# BMS_Battery_Connections.net
KiCad netlist of a schematic drawn in Altium Designer
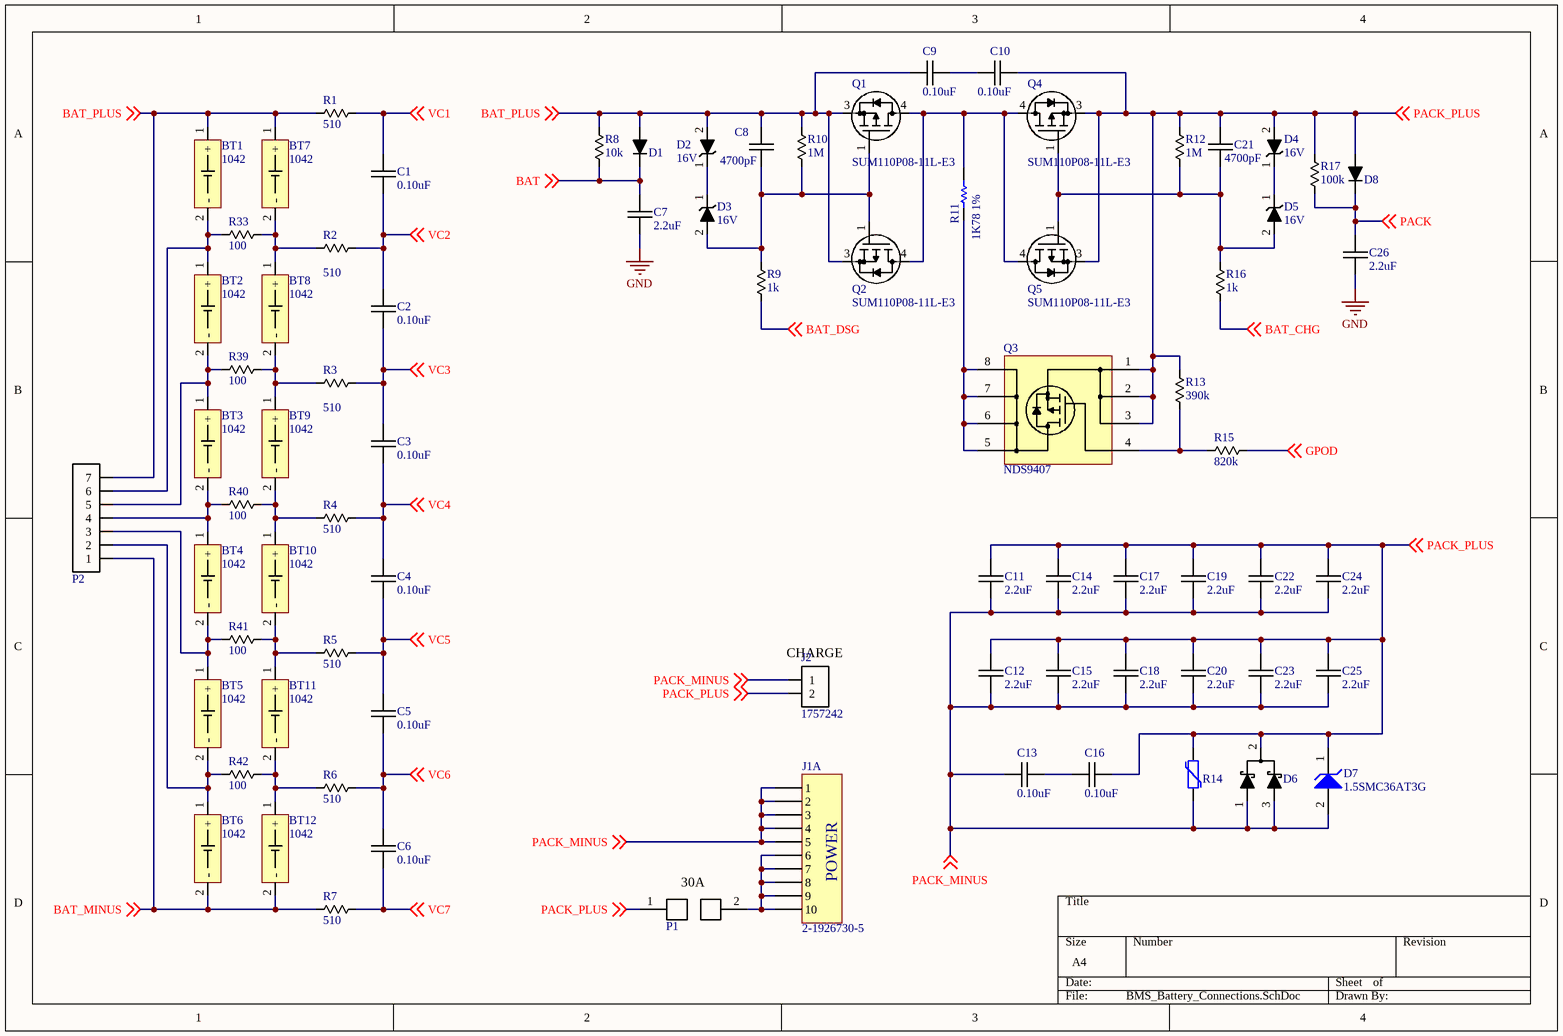
[diagram p0: BMS_Battery_Connections.SchDoc]

(export (version "E")
  (design (tool "Eeschema 10.0.6"))
  (components
    (comp (ref "BT1")
      (value "1042")
      (footprint "KEYSTONE_1042")
      (description "Battery Holder, 18650, SMD")
      (fields (field (name "PART NUMBER") "CONN-00077") (field (name "MANUFACTURER") "Keystone"))
      (libsource (lib "Connectors$") (part "CONN-00077"))
    )
    (comp (ref "BT2")
      (value "1042")
      (footprint "KEYSTONE_1042")
      (description "Battery Holder, 18650, SMD")
      (fields (field (name "PART NUMBER") "CONN-00077") (field (name "MANUFACTURER") "Keystone"))
      (libsource (lib "Connectors$") (part "CONN-00077"))
    )
    (comp (ref "BT3")
      (value "1042")
      (footprint "KEYSTONE_1042")
      (description "Battery Holder, 18650, SMD")
      (fields (field (name "PART NUMBER") "CONN-00077") (field (name "MANUFACTURER") "Keystone"))
      (libsource (lib "Connectors$") (part "CONN-00077"))
    )
    (comp (ref "BT4")
      (value "1042")
      (footprint "KEYSTONE_1042")
      (description "Battery Holder, 18650, SMD")
      (fields (field (name "PART NUMBER") "CONN-00077") (field (name "MANUFACTURER") "Keystone"))
      (libsource (lib "Connectors$") (part "CONN-00077"))
    )
    (comp (ref "BT5")
      (value "1042")
      (footprint "KEYSTONE_1042")
      (description "Battery Holder, 18650, SMD")
      (fields (field (name "PART NUMBER") "CONN-00077") (field (name "MANUFACTURER") "Keystone"))
      (libsource (lib "Connectors$") (part "CONN-00077"))
    )
    (comp (ref "BT6")
      (value "1042")
      (footprint "KEYSTONE_1042")
      (description "Battery Holder, 18650, SMD")
      (fields (field (name "PART NUMBER") "CONN-00077") (field (name "MANUFACTURER") "Keystone"))
      (libsource (lib "Connectors$") (part "CONN-00077"))
    )
    (comp (ref "BT7")
      (value "1042")
      (footprint "KEYSTONE_1042")
      (description "Battery Holder, 18650, SMD")
      (fields (field (name "PART NUMBER") "CONN-00077") (field (name "MANUFACTURER") "Keystone"))
      (libsource (lib "Connectors$") (part "CONN-00077"))
    )
    (comp (ref "BT8")
      (value "1042")
      (footprint "KEYSTONE_1042")
      (description "Battery Holder, 18650, SMD")
      (fields (field (name "PART NUMBER") "CONN-00077") (field (name "MANUFACTURER") "Keystone"))
      (libsource (lib "Connectors$") (part "CONN-00077"))
    )
    (comp (ref "BT9")
      (value "1042")
      (footprint "KEYSTONE_1042")
      (description "Battery Holder, 18650, SMD")
      (fields (field (name "PART NUMBER") "CONN-00077") (field (name "MANUFACTURER") "Keystone"))
      (libsource (lib "Connectors$") (part "CONN-00077"))
    )
    (comp (ref "BT10")
      (value "1042")
      (footprint "KEYSTONE_1042")
      (description "Battery Holder, 18650, SMD")
      (fields (field (name "PART NUMBER") "CONN-00077") (field (name "MANUFACTURER") "Keystone"))
      (libsource (lib "Connectors$") (part "CONN-00077"))
    )
    (comp (ref "BT11")
      (value "1042")
      (footprint "KEYSTONE_1042")
      (description "Battery Holder, 18650, SMD")
      (fields (field (name "PART NUMBER") "CONN-00077") (field (name "MANUFACTURER") "Keystone"))
      (libsource (lib "Connectors$") (part "CONN-00077"))
    )
    (comp (ref "BT12")
      (value "1042")
      (footprint "KEYSTONE_1042")
      (description "Battery Holder, 18650, SMD")
      (fields (field (name "PART NUMBER") "CONN-00077") (field (name "MANUFACTURER") "Keystone"))
      (libsource (lib "Connectors$") (part "CONN-00077"))
    )
    (comp (ref "C1")
      (value "0.10uF")
      (footprint "chip_0805")
      (description "CAP, 0.10uF, 10%, 50V, X7R, 0805")
      (fields (field (name "PART NUMBER") "CAP-00072") (field (name "TOLERANCE") "10%"))
      (libsource (lib "Capacitors$") (part "CAP-00072"))
    )
    (comp (ref "C2")
      (value "0.10uF")
      (footprint "chip_0805")
      (description "CAP, 0.10uF, 10%, 50V, X7R, 0805")
      (fields (field (name "PART NUMBER") "CAP-00072") (field (name "TOLERANCE") "10%"))
      (libsource (lib "Capacitors$") (part "CAP-00072"))
    )
    (comp (ref "C3")
      (value "0.10uF")
      (footprint "chip_0805")
      (description "CAP, 0.10uF, 10%, 50V, X7R, 0805")
      (fields (field (name "PART NUMBER") "CAP-00072") (field (name "TOLERANCE") "10%"))
      (libsource (lib "Capacitors$") (part "CAP-00072"))
    )
    (comp (ref "C4")
      (value "0.10uF")
      (footprint "chip_0805")
      (description "CAP, 0.10uF, 10%, 50V, X7R, 0805")
      (fields (field (name "PART NUMBER") "CAP-00072") (field (name "TOLERANCE") "10%"))
      (libsource (lib "Capacitors$") (part "CAP-00072"))
    )
    (comp (ref "C5")
      (value "0.10uF")
      (footprint "chip_0805")
      (description "CAP, 0.10uF, 10%, 50V, X7R, 0805")
      (fields (field (name "PART NUMBER") "CAP-00072") (field (name "TOLERANCE") "10%"))
      (libsource (lib "Capacitors$") (part "CAP-00072"))
    )
    (comp (ref "C6")
      (value "0.10uF")
      (footprint "chip_0805")
      (description "CAP, 0.10uF, 10%, 50V, X7R, 0805")
      (fields (field (name "PART NUMBER") "CAP-00072") (field (name "TOLERANCE") "10%"))
      (libsource (lib "Capacitors$") (part "CAP-00072"))
    )
    (comp (ref "C7")
      (value "2.2uF")
      (footprint "chip_1210")
      (description "CAP, 2.2uF, ±20%, 100V, X7R, 0603")
      (fields (field (name "PART NUMBER") "CAP-00536") (field (name "TOLERANCE") "±20%"))
      (libsource (lib "Capacitors$") (part "CAP-00536"))
    )
    (comp (ref "C8")
      (value "4700pF")
      (footprint "chip_0805")
      (description "CAP, 4700pF, 10%, 100V, X7R, 0805")
      (fields (field (name "PART NUMBER") "CAP-00032") (field (name "TOLERANCE") "10%"))
      (libsource (lib "Capacitors$") (part "CAP-00032"))
    )
    (comp (ref "C9")
      (value "0.10uF")
      (footprint "chip_0805")
      (description "CAP, 0.10uF, 10%, 50V, X7R, 0805")
      (fields (field (name "PART NUMBER") "CAP-00072") (field (name "TOLERANCE") "10%"))
      (libsource (lib "Capacitors$") (part "CAP-00072"))
    )
    (comp (ref "C10")
      (value "0.10uF")
      (footprint "chip_0805")
      (description "CAP, 0.10uF, 10%, 50V, X7R, 0805")
      (fields (field (name "PART NUMBER") "CAP-00072") (field (name "TOLERANCE") "10%"))
      (libsource (lib "Capacitors$") (part "CAP-00072"))
    )
    (comp (ref "C11")
      (value "2.2uF")
      (footprint "chip_1210")
      (description "CAP, 2.2uF, ±20%, 100V, X7R, 0603")
      (fields (field (name "PART NUMBER") "CAP-00536") (field (name "TOLERANCE") "±20%"))
      (libsource (lib "Capacitors$") (part "CAP-00536"))
    )
    (comp (ref "C12")
      (value "2.2uF")
      (footprint "chip_1210")
      (description "CAP, 2.2uF, ±20%, 100V, X7R, 0603")
      (fields (field (name "PART NUMBER") "CAP-00536") (field (name "TOLERANCE") "±20%"))
      (libsource (lib "Capacitors$") (part "CAP-00536"))
    )
    (comp (ref "C13")
      (value "0.10uF")
      (footprint "chip_0805")
      (description "CAP, 0.10uF, 10%, 50V, X7R, 0805")
      (fields (field (name "PART NUMBER") "CAP-00072") (field (name "TOLERANCE") "10%"))
      (libsource (lib "Capacitors$") (part "CAP-00072"))
    )
    (comp (ref "C14")
      (value "2.2uF")
      (footprint "chip_1210")
      (description "CAP, 2.2uF, ±20%, 100V, X7R, 0603")
      (fields (field (name "PART NUMBER") "CAP-00536") (field (name "TOLERANCE") "±20%"))
      (libsource (lib "Capacitors$") (part "CAP-00536"))
    )
    (comp (ref "C15")
      (value "2.2uF")
      (footprint "chip_1210")
      (description "CAP, 2.2uF, ±20%, 100V, X7R, 0603")
      (fields (field (name "PART NUMBER") "CAP-00536") (field (name "TOLERANCE") "±20%"))
      (libsource (lib "Capacitors$") (part "CAP-00536"))
    )
    (comp (ref "C16")
      (value "0.10uF")
      (footprint "chip_0805")
      (description "CAP, 0.10uF, 10%, 50V, X7R, 0805")
      (fields (field (name "PART NUMBER") "CAP-00072") (field (name "TOLERANCE") "10%"))
      (libsource (lib "Capacitors$") (part "CAP-00072"))
    )
    (comp (ref "C17")
      (value "2.2uF")
      (footprint "chip_1210")
      (description "CAP, 2.2uF, ±20%, 100V, X7R, 0603")
      (fields (field (name "PART NUMBER") "CAP-00536") (field (name "TOLERANCE") "±20%"))
      (libsource (lib "Capacitors$") (part "CAP-00536"))
    )
    (comp (ref "C18")
      (value "2.2uF")
      (footprint "chip_1210")
      (description "CAP, 2.2uF, ±20%, 100V, X7R, 0603")
      (fields (field (name "PART NUMBER") "CAP-00536") (field (name "TOLERANCE") "±20%"))
      (libsource (lib "Capacitors$") (part "CAP-00536"))
    )
    (comp (ref "C19")
      (value "2.2uF")
      (footprint "chip_1210")
      (description "CAP, 2.2uF, ±20%, 100V, X7R, 0603")
      (fields (field (name "PART NUMBER") "CAP-00536") (field (name "TOLERANCE") "±20%"))
      (libsource (lib "Capacitors$") (part "CAP-00536"))
    )
    (comp (ref "C20")
      (value "2.2uF")
      (footprint "chip_1210")
      (description "CAP, 2.2uF, ±20%, 100V, X7R, 0603")
      (fields (field (name "PART NUMBER") "CAP-00536") (field (name "TOLERANCE") "±20%"))
      (libsource (lib "Capacitors$") (part "CAP-00536"))
    )
    (comp (ref "C21")
      (value "4700pF")
      (footprint "chip_0805")
      (description "CAP, 4700pF, 10%, 100V, X7R, 0805")
      (fields (field (name "PART NUMBER") "CAP-00032") (field (name "TOLERANCE") "10%"))
      (libsource (lib "Capacitors$") (part "CAP-00032"))
    )
    (comp (ref "C22")
      (value "2.2uF")
      (footprint "chip_1210")
      (description "CAP, 2.2uF, ±20%, 100V, X7R, 0603")
      (fields (field (name "PART NUMBER") "CAP-00536") (field (name "TOLERANCE") "±20%"))
      (libsource (lib "Capacitors$") (part "CAP-00536"))
    )
    (comp (ref "C23")
      (value "2.2uF")
      (footprint "chip_1210")
      (description "CAP, 2.2uF, ±20%, 100V, X7R, 0603")
      (fields (field (name "PART NUMBER") "CAP-00536") (field (name "TOLERANCE") "±20%"))
      (libsource (lib "Capacitors$") (part "CAP-00536"))
    )
    (comp (ref "C24")
      (value "2.2uF")
      (footprint "chip_1210")
      (description "CAP, 2.2uF, ±20%, 100V, X7R, 0603")
      (fields (field (name "PART NUMBER") "CAP-00536") (field (name "TOLERANCE") "±20%"))
      (libsource (lib "Capacitors$") (part "CAP-00536"))
    )
    (comp (ref "C25")
      (value "2.2uF")
      (footprint "chip_1210")
      (description "CAP, 2.2uF, ±20%, 100V, X7R, 0603")
      (fields (field (name "PART NUMBER") "CAP-00536") (field (name "TOLERANCE") "±20%"))
      (libsource (lib "Capacitors$") (part "CAP-00536"))
    )
    (comp (ref "C26")
      (value "2.2uF")
      (footprint "chip_1210")
      (description "CAP, 2.2uF, ±20%, 100V, X7R, 0603")
      (fields (field (name "PART NUMBER") "CAP-00536") (field (name "TOLERANCE") "±20%"))
      (libsource (lib "Capacitors$") (part "CAP-00536"))
    )
    (comp (ref "D1")
      (value "diode_0")
      (footprint "sod123_0")
      (description "Dio, Silicon, 200mA, 1V, 100V, SOD-123")
      (fields (field (name "PART NUMBER") "DIO-00060") (field (name "MANUFACTURER") "ON Semi"))
      (libsource (lib "Diodes$") (part "DIO-00060"))
    )
    (comp (ref "D2")
      (value "16V")
      (footprint "sod523_0")
      (description "Dio, Zener, 16V 300mW, SOD-523")
      (fields (field (name "PART NUMBER") "DIO-00082") (field (name "TOLERANCE") "5%"))
      (libsource (lib "Diodes$") (part "DIO-00082"))
    )
    (comp (ref "D3")
      (value "16V")
      (footprint "sod523_0")
      (description "Dio, Zener, 16V 300mW, SOD-523")
      (fields (field (name "PART NUMBER") "DIO-00082") (field (name "TOLERANCE") "5%"))
      (libsource (lib "Diodes$") (part "DIO-00082"))
    )
    (comp (ref "D4")
      (value "16V")
      (footprint "sod523_0")
      (description "Dio, Zener, 16V 300mW, SOD-523")
      (fields (field (name "PART NUMBER") "DIO-00082") (field (name "TOLERANCE") "5%"))
      (libsource (lib "Diodes$") (part "DIO-00082"))
    )
    (comp (ref "D5")
      (value "16V")
      (footprint "sod523_0")
      (description "Dio, Zener, 16V 300mW, SOD-523")
      (fields (field (name "PART NUMBER") "DIO-00082") (field (name "TOLERANCE") "5%"))
      (libsource (lib "Diodes$") (part "DIO-00082"))
    )
    (comp (ref "D6")
      (value "V40PWM10C-M3/I")
      (footprint "DPAK_SLIM")
      (description "Dio, Schottky Array, Dual, Common Cathode, 100V 20A, SLIM DPAK")
      (fields (field (name "PART NUMBER") "DIO-00081") (field (name "MANUFACTURER") "Vishay"))
      (libsource (lib "Diodes$") (part "DIO-00081"))
    )
    (comp (ref "D7")
      (value "1.5SMC36AT3G")
      (footprint "ONSC-SMC-2-403-03_V")
      (fields (field (name "MANUFACTURER") "On Semiconductor"))
      (libsource (lib "Altium Content Vault") (part "ONSC-K1A2-2"))
    )
    (comp (ref "D8")
      (value "diode_0")
      (footprint "sod123_0")
      (description "Dio, Silicon, 200mA, 1V, 100V, SOD-123")
      (fields (field (name "PART NUMBER") "DIO-00060") (field (name "MANUFACTURER") "ON Semi"))
      (libsource (lib "Diodes$") (part "DIO-00060"))
    )
    (comp (ref "J1")
      (value "2-1926730-5")
      (footprint "TE_CONN_2-1926730-5")
      (description "Backplane Header, Blades and Pins, Edge Mount Right Angle, 10 Power 25 Signal")
      (fields (field (name "PART NUMBER") "CONN-00093") (field (name "MANUFACTURER") "TE Connectivity"))
      (libsource (lib "Connectors$") (part "CONN-00093"))
    )
    (comp (ref "J2")
      (value "1757242")
      (footprint "PHOENIX_1757242")
      (description "Terminal Blk Header, 2 Pos, 5.08mm, 12A, Right-Angle")
      (fields (field (name "PART NUMBER") "CONN-00102") (field (name "MANUFACTURER") "Phoenix Contact"))
      (libsource (lib "Connectors$") (part "CONN-00102"))
    )
    (comp (ref "P1")
      (value "conn-fuse-holder_0")
      (footprint "FUSE_HOLDER_KEYSTONE_3557-2")
      (description "Fuse Holder, 30A, 500V, LP-Mini 897, ATOF 257")
      (fields (field (name "PART NUMBER") "CONN-00015") (field (name "MANUFACTURER") "Keystone Electronics"))
      (libsource (lib "Connectors$") (part "CONN-00015"))
    )
    (comp (ref "P2")
      (value "conn-7x1_0")
      (footprint "HDDR_7x1_0")
      (description "Header, 7x1, 0.1\"")
      (fields (field (name "PART NUMBER") "CONN-00105") (field (name "MANUFACTURER") "Samtec"))
      (libsource (lib "Connectors$") (part "CONN-00105"))
    )
    (comp (ref "Q1")
      (value "SUM110P08-11L-E3")
      (footprint "D2PAK-3_1")
      (description "XSTR, MOSFET P-Channel, 80V 110A, D2PAK")
      (fields (field (name "PART NUMBER") "XSTR-00050") (field (name "MANUFACTURER") "Vishay Siliconix"))
      (libsource (lib "Transistors$") (part "XSTR-00050"))
    )
    (comp (ref "Q2")
      (value "SUM110P08-11L-E3")
      (footprint "D2PAK-3_1")
      (description "XSTR, MOSFET P-Channel, 80V 110A, D2PAK")
      (fields (field (name "PART NUMBER") "XSTR-00050") (field (name "MANUFACTURER") "Vishay Siliconix"))
      (libsource (lib "Transistors$") (part "XSTR-00050"))
    )
    (comp (ref "Q3")
      (value "NDS9407")
      (footprint "SO-8")
      (description "XSTR PFET, 3A, 60V, 2.5W, SOIC-8")
      (fields (field (name "PART NUMBER") "XSTR-00036") (field (name "MANUFACTURER") "ON Semi"))
      (libsource (lib "Transistors$") (part "XSTR-00036"))
    )
    (comp (ref "Q4")
      (value "SUM110P08-11L-E3")
      (footprint "D2PAK-3_1")
      (description "XSTR, MOSFET P-Channel, 80V 110A, D2PAK")
      (fields (field (name "PART NUMBER") "XSTR-00050") (field (name "MANUFACTURER") "Vishay Siliconix"))
      (libsource (lib "Transistors$") (part "XSTR-00050"))
    )
    (comp (ref "Q5")
      (value "SUM110P08-11L-E3")
      (footprint "D2PAK-3_1")
      (description "XSTR, MOSFET P-Channel, 80V 110A, D2PAK")
      (fields (field (name "PART NUMBER") "XSTR-00050") (field (name "MANUFACTURER") "Vishay Siliconix"))
      (libsource (lib "Transistors$") (part "XSTR-00050"))
    )
    (comp (ref "R1")
      (value "510")
      (footprint "chip_0805")
      (description "RES SMD 510 OHM 1% 1/8W 0805")
      (fields (field (name "PART NUMBER") "RES-00240") (field (name "TOLERANCE") "1%"))
      (libsource (lib "Resistors$") (part "RES-00240"))
    )
    (comp (ref "R2")
      (value "510")
      (footprint "chip_0805")
      (description "RES SMD 510 OHM 1% 1/8W 0805")
      (fields (field (name "PART NUMBER") "RES-00240") (field (name "TOLERANCE") "1%"))
      (libsource (lib "Resistors$") (part "RES-00240"))
    )
    (comp (ref "R3")
      (value "510")
      (footprint "chip_0805")
      (description "RES SMD 510 OHM 1% 1/8W 0805")
      (fields (field (name "PART NUMBER") "RES-00240") (field (name "TOLERANCE") "1%"))
      (libsource (lib "Resistors$") (part "RES-00240"))
    )
    (comp (ref "R4")
      (value "510")
      (footprint "chip_0805")
      (description "RES SMD 510 OHM 1% 1/8W 0805")
      (fields (field (name "PART NUMBER") "RES-00240") (field (name "TOLERANCE") "1%"))
      (libsource (lib "Resistors$") (part "RES-00240"))
    )
    (comp (ref "R5")
      (value "510")
      (footprint "chip_0805")
      (description "RES SMD 510 OHM 1% 1/8W 0805")
      (fields (field (name "PART NUMBER") "RES-00240") (field (name "TOLERANCE") "1%"))
      (libsource (lib "Resistors$") (part "RES-00240"))
    )
    (comp (ref "R6")
      (value "510")
      (footprint "chip_0805")
      (description "RES SMD 510 OHM 1% 1/8W 0805")
      (fields (field (name "PART NUMBER") "RES-00240") (field (name "TOLERANCE") "1%"))
      (libsource (lib "Resistors$") (part "RES-00240"))
    )
    (comp (ref "R7")
      (value "510")
      (footprint "chip_0805")
      (description "RES SMD 510 OHM 1% 1/8W 0805")
      (fields (field (name "PART NUMBER") "RES-00240") (field (name "TOLERANCE") "1%"))
      (libsource (lib "Resistors$") (part "RES-00240"))
    )
    (comp (ref "R8")
      (value "10k")
      (footprint "chip_0805")
      (description "RES SMD 10K OHM 1% 1/8W 0805")
      (fields (field (name "PART NUMBER") "RES-00307") (field (name "TOLERANCE") "1%"))
      (libsource (lib "Resistors$") (part "RES-00307"))
    )
    (comp (ref "R9")
      (value "1k")
      (footprint "chip_0805")
      (description "RES SMD 1K OHM 1% 1/8W 0805")
      (fields (field (name "PART NUMBER") "RES-00361") (field (name "TOLERANCE") "1%"))
      (libsource (lib "Resistors$") (part "RES-00361"))
    )
    (comp (ref "R10")
      (value "1M")
      (footprint "chip_0805")
      (description "RES SMD 1M OHM 1% 1/8W 0805")
      (fields (field (name "PART NUMBER") "RES-00363") (field (name "TOLERANCE") "1%"))
      (libsource (lib "Resistors$") (part "RES-00363"))
    )
    (comp (ref "R11")
      (value "1K78 1%")
      (footprint "RESC2512(6432)_L")
      (description "1K78 1W 1% 2512 (6432 Metric)  SMD")
      (fields (field (name "TOLERANCE") "1 %") (field (name "POWER") "1 W"))
      (libsource (lib "Altium Content Vault") (part "RES"))
    )
    (comp (ref "R12")
      (value "1M")
      (footprint "chip_0805")
      (description "RES SMD 1M OHM 1% 1/8W 0805")
      (fields (field (name "PART NUMBER") "RES-00363") (field (name "TOLERANCE") "1%"))
      (libsource (lib "Resistors$") (part "RES-00363"))
    )
    (comp (ref "R13")
      (value "390k")
      (footprint "chip_0805")
      (description "RES SMD 390K OHM 1% 1/8W 0805")
      (fields (field (name "PART NUMBER") "RES-00455") (field (name "TOLERANCE") "1%"))
      (libsource (lib "Resistors$") (part "RES-00455"))
    )
    (comp (ref "R14")
      (value "MOV_0")
      (footprint "chip_1210")
      (description "Varistor, Ceramic, 47V 300A 2J, 1210")
      (fields (field (name "PART NUMBER") "MISC-00057") (field (name "MANUFACTURER") "TDK"))
      (libsource (lib "Misc$") (part "MISC-00057"))
    )
    (comp (ref "R15")
      (value "820k")
      (footprint "chip_0805")
      (description "RES SMD 820K OHM 1% 1/8W 0805")
      (fields (field (name "PART NUMBER") "RES-00567") (field (name "TOLERANCE") "1%"))
      (libsource (lib "Resistors$") (part "RES-00567"))
    )
    (comp (ref "R16")
      (value "1k")
      (footprint "chip_0805")
      (description "RES SMD 1K OHM 1% 1/8W 0805")
      (fields (field (name "PART NUMBER") "RES-00361") (field (name "TOLERANCE") "1%"))
      (libsource (lib "Resistors$") (part "RES-00361"))
    )
    (comp (ref "R17")
      (value "100k")
      (footprint "chip_0805")
      (description "RES SMD 100K OHM 1% 1/8W 0805")
      (fields (field (name "PART NUMBER") "RES-00302") (field (name "TOLERANCE") "1%"))
      (libsource (lib "Resistors$") (part "RES-00302"))
    )
    (comp (ref "R33")
      (value "100")
      (footprint "chip_0805")
      (description "RES SMD 100 OHM 1% 1/8W 0805")
      (fields (field (name "PART NUMBER") "RES-00179") (field (name "TOLERANCE") "1%"))
      (libsource (lib "Resistors$") (part "RES-00179"))
    )
    (comp (ref "R39")
      (value "100")
      (footprint "chip_0805")
      (description "RES SMD 100 OHM 1% 1/8W 0805")
      (fields (field (name "PART NUMBER") "RES-00179") (field (name "TOLERANCE") "1%"))
      (libsource (lib "Resistors$") (part "RES-00179"))
    )
    (comp (ref "R40")
      (value "100")
      (footprint "chip_0805")
      (description "RES SMD 100 OHM 1% 1/8W 0805")
      (fields (field (name "PART NUMBER") "RES-00179") (field (name "TOLERANCE") "1%"))
      (libsource (lib "Resistors$") (part "RES-00179"))
    )
    (comp (ref "R41")
      (value "100")
      (footprint "chip_0805")
      (description "RES SMD 100 OHM 1% 1/8W 0805")
      (fields (field (name "PART NUMBER") "RES-00179") (field (name "TOLERANCE") "1%"))
      (libsource (lib "Resistors$") (part "RES-00179"))
    )
    (comp (ref "R42")
      (value "100")
      (footprint "chip_0805")
      (description "RES SMD 100 OHM 1% 1/8W 0805")
      (fields (field (name "PART NUMBER") "RES-00179") (field (name "TOLERANCE") "1%"))
      (libsource (lib "Resistors$") (part "RES-00179"))
    )
  )
  (nets
    (net (code "1") (name "BAT") (class "Default")
      (node (ref "C7") (pin "1") (pinfunction "1_1") (pintype "passive"))
      (node (ref "D1") (pin "1") (pinfunction "1_1") (pintype "passive"))
      (node (ref "R8") (pin "2") (pinfunction "2_2") (pintype "passive"))
    )
    (net (code "2") (name "BAT_CHG") (class "Default")
      (node (ref "R16") (pin "2") (pinfunction "2_2") (pintype "passive"))
    )
    (net (code "3") (name "BAT_DSG") (class "Default")
      (node (ref "R9") (pin "2") (pinfunction "2_2") (pintype "passive"))
    )
    (net (code "4") (name "BAT_MINUS") (class "Default")
      (node (ref "BT12") (pin "2") (pinfunction "-_2") (pintype "passive"))
      (node (ref "BT6") (pin "2") (pinfunction "-_2") (pintype "passive"))
      (node (ref "P2") (pin "1") (pinfunction "1_1") (pintype "passive"))
      (node (ref "R7") (pin "1") (pinfunction "1_1") (pintype "passive"))
    )
    (net (code "5") (name "BAT_PLUS") (class "Default")
      (node (ref "BT1") (pin "1") (pinfunction "+_1") (pintype "passive"))
      (node (ref "BT7") (pin "1") (pinfunction "+_1") (pintype "passive"))
      (node (ref "C8") (pin "1") (pinfunction "1_1") (pintype "passive"))
      (node (ref "C9") (pin "1") (pinfunction "1_1") (pintype "passive"))
      (node (ref "D1") (pin "2") (pinfunction "2_2") (pintype "passive"))
      (node (ref "D2") (pin "2") (pinfunction "2_2") (pintype "passive"))
      (node (ref "P2") (pin "7") (pinfunction "7_7") (pintype "passive"))
      (node (ref "Q1") (pin "3") (pinfunction "S_3") (pintype "passive"))
      (node (ref "Q2") (pin "3") (pinfunction "S_3") (pintype "passive"))
      (node (ref "R1") (pin "1") (pinfunction "1_1") (pintype "passive"))
      (node (ref "R10") (pin "1") (pinfunction "1_1") (pintype "passive"))
      (node (ref "R8") (pin "1") (pinfunction "1_1") (pintype "passive"))
    )
    (net (code "6") (name "GND") (class "Default")
      (node (ref "C26") (pin "2") (pinfunction "2_2") (pintype "passive"))
      (node (ref "C7") (pin "2") (pinfunction "2_2") (pintype "passive"))
    )
    (net (code "7") (name "GPOD") (class "Default")
      (node (ref "R15") (pin "2") (pinfunction "2_2") (pintype "passive"))
    )
    (net (code "8") (name "Net-(BT1--)") (class "Default")
      (node (ref "BT1") (pin "2") (pinfunction "-_2") (pintype "passive"))
      (node (ref "BT2") (pin "1") (pinfunction "+_1") (pintype "passive"))
      (node (ref "P2") (pin "6") (pinfunction "6_6") (pintype "passive"))
      (node (ref "R33") (pin "1") (pinfunction "1_1") (pintype "passive"))
    )
    (net (code "9") (name "Net-(BT2--)") (class "Default")
      (node (ref "BT2") (pin "2") (pinfunction "-_2") (pintype "passive"))
      (node (ref "BT3") (pin "1") (pinfunction "+_1") (pintype "passive"))
      (node (ref "P2") (pin "5") (pinfunction "5_5") (pintype "passive"))
      (node (ref "R39") (pin "1") (pinfunction "1_1") (pintype "passive"))
    )
    (net (code "10") (name "Net-(BT3--)") (class "Default")
      (node (ref "BT3") (pin "2") (pinfunction "-_2") (pintype "passive"))
      (node (ref "BT4") (pin "1") (pinfunction "+_1") (pintype "passive"))
      (node (ref "P2") (pin "4") (pinfunction "4_4") (pintype "passive"))
      (node (ref "R40") (pin "1") (pinfunction "1_1") (pintype "passive"))
    )
    (net (code "11") (name "Net-(BT4--)") (class "Default")
      (node (ref "BT4") (pin "2") (pinfunction "-_2") (pintype "passive"))
      (node (ref "BT5") (pin "1") (pinfunction "+_1") (pintype "passive"))
      (node (ref "P2") (pin "3") (pinfunction "3_3") (pintype "passive"))
      (node (ref "R41") (pin "1") (pinfunction "1_1") (pintype "passive"))
    )
    (net (code "12") (name "Net-(BT5--)") (class "Default")
      (node (ref "BT5") (pin "2") (pinfunction "-_2") (pintype "passive"))
      (node (ref "BT6") (pin "1") (pinfunction "+_1") (pintype "passive"))
      (node (ref "P2") (pin "2") (pinfunction "2_2") (pintype "passive"))
      (node (ref "R42") (pin "1") (pinfunction "1_1") (pintype "passive"))
    )
    (net (code "13") (name "Net-(BT7--)") (class "Default")
      (node (ref "BT7") (pin "2") (pinfunction "-_2") (pintype "passive"))
      (node (ref "BT8") (pin "1") (pinfunction "+_1") (pintype "passive"))
      (node (ref "R2") (pin "1") (pinfunction "1_1") (pintype "passive"))
      (node (ref "R33") (pin "2") (pinfunction "2_2") (pintype "passive"))
    )
    (net (code "14") (name "Net-(BT8--)") (class "Default")
      (node (ref "BT8") (pin "2") (pinfunction "-_2") (pintype "passive"))
      (node (ref "BT9") (pin "1") (pinfunction "+_1") (pintype "passive"))
      (node (ref "R3") (pin "1") (pinfunction "1_1") (pintype "passive"))
      (node (ref "R39") (pin "2") (pinfunction "2_2") (pintype "passive"))
    )
    (net (code "15") (name "Net-(BT10-+)") (class "Default")
      (node (ref "BT10") (pin "1") (pinfunction "+_1") (pintype "passive"))
      (node (ref "BT9") (pin "2") (pinfunction "-_2") (pintype "passive"))
      (node (ref "R4") (pin "1") (pinfunction "1_1") (pintype "passive"))
      (node (ref "R40") (pin "2") (pinfunction "2_2") (pintype "passive"))
    )
    (net (code "16") (name "Net-(BT10--)") (class "Default")
      (node (ref "BT10") (pin "2") (pinfunction "-_2") (pintype "passive"))
      (node (ref "BT11") (pin "1") (pinfunction "+_1") (pintype "passive"))
      (node (ref "R41") (pin "2") (pinfunction "2_2") (pintype "passive"))
      (node (ref "R5") (pin "1") (pinfunction "1_1") (pintype "passive"))
    )
    (net (code "17") (name "Net-(BT11--)") (class "Default")
      (node (ref "BT11") (pin "2") (pinfunction "-_2") (pintype "passive"))
      (node (ref "BT12") (pin "1") (pinfunction "+_1") (pintype "passive"))
      (node (ref "R42") (pin "2") (pinfunction "2_2") (pintype "passive"))
      (node (ref "R6") (pin "1") (pinfunction "1_1") (pintype "passive"))
    )
    (net (code "18") (name "Net-(C10-Pad1)") (class "Default")
      (node (ref "C10") (pin "1") (pinfunction "1_1") (pintype "passive"))
      (node (ref "C9") (pin "2") (pinfunction "2_2") (pintype "passive"))
    )
    (net (code "19") (name "Net-(C13-Pad1)") (class "Default")
      (node (ref "C13") (pin "1") (pinfunction "1_1") (pintype "passive"))
      (node (ref "C16") (pin "2") (pinfunction "2_2") (pintype "passive"))
    )
    (net (code "20") (name "Net-(D2-Pad1)") (class "Default")
      (node (ref "D2") (pin "1") (pinfunction "1_1") (pintype "passive"))
      (node (ref "D3") (pin "1") (pinfunction "1_1") (pintype "passive"))
    )
    (net (code "21") (name "Net-(D4-Pad1)") (class "Default")
      (node (ref "D4") (pin "1") (pinfunction "1_1") (pintype "passive"))
      (node (ref "D5") (pin "1") (pinfunction "1_1") (pintype "passive"))
    )
    (net (code "22") (name "Net-(J1-Pad10)") (class "Default")
      (node (ref "J1") (pin "10") (pinfunction "10_10") (pintype "passive"))
      (node (ref "J1") (pin "6") (pinfunction "6_6") (pintype "passive"))
      (node (ref "J1") (pin "7") (pinfunction "7_7") (pintype "passive"))
      (node (ref "J1") (pin "8") (pinfunction "8_8") (pintype "passive"))
      (node (ref "J1") (pin "9") (pinfunction "9_9") (pintype "passive"))
      (node (ref "P1") (pin "2") (pinfunction "2_2") (pintype "passive"))
    )
    (net (code "23") (name "Net-(Q1-D)") (class "Default")
      (node (ref "Q1") (pin "4") (pinfunction "D_4") (pintype "passive"))
      (node (ref "Q2") (pin "4") (pinfunction "D_4") (pintype "passive"))
      (node (ref "Q4") (pin "4") (pinfunction "D_4") (pintype "passive"))
      (node (ref "Q5") (pin "4") (pinfunction "D_4") (pintype "passive"))
      (node (ref "R11") (pin "2") (pinfunction "2_2") (pintype "passive"))
    )
    (net (code "24") (name "Net-(Q1-G)") (class "Default")
      (node (ref "C8") (pin "2") (pinfunction "2_2") (pintype "passive"))
      (node (ref "D3") (pin "2") (pinfunction "2_2") (pintype "passive"))
      (node (ref "Q1") (pin "1") (pinfunction "G_1") (pintype "passive"))
      (node (ref "Q2") (pin "1") (pinfunction "G_1") (pintype "passive"))
      (node (ref "R10") (pin "2") (pinfunction "2_2") (pintype "passive"))
      (node (ref "R9") (pin "1") (pinfunction "1_1") (pintype "passive"))
    )
    (net (code "25") (name "Net-(Q3-D-Pad5)") (class "Default")
      (node (ref "Q3") (pin "5") (pinfunction "D_5") (pintype "passive"))
      (node (ref "Q3") (pin "6") (pinfunction "D_6") (pintype "passive"))
      (node (ref "Q3") (pin "7") (pinfunction "D_7") (pintype "passive"))
      (node (ref "Q3") (pin "8") (pinfunction "D_8") (pintype "passive"))
      (node (ref "R11") (pin "1") (pinfunction "1_1") (pintype "passive"))
    )
    (net (code "26") (name "Net-(Q3-G)") (class "Default")
      (node (ref "Q3") (pin "4") (pinfunction "G_4") (pintype "passive"))
      (node (ref "R13") (pin "2") (pinfunction "2_2") (pintype "passive"))
      (node (ref "R15") (pin "1") (pinfunction "1_1") (pintype "passive"))
    )
    (net (code "27") (name "Net-(Q4-G)") (class "Default")
      (node (ref "C21") (pin "2") (pinfunction "2_2") (pintype "passive"))
      (node (ref "D5") (pin "2") (pinfunction "2_2") (pintype "passive"))
      (node (ref "Q4") (pin "1") (pinfunction "G_1") (pintype "passive"))
      (node (ref "Q5") (pin "1") (pinfunction "G_1") (pintype "passive"))
      (node (ref "R12") (pin "2") (pinfunction "2_2") (pintype "passive"))
      (node (ref "R16") (pin "1") (pinfunction "1_1") (pintype "passive"))
    )
    (net (code "28") (name "PACK") (class "Default")
      (node (ref "C26") (pin "1") (pinfunction "1_1") (pintype "passive"))
      (node (ref "D8") (pin "1") (pinfunction "1_1") (pintype "passive"))
      (node (ref "R17") (pin "2") (pinfunction "2_2") (pintype "passive"))
    )
    (net (code "29") (name "PACK_MINUS") (class "Default")
      (node (ref "C11") (pin "2") (pinfunction "2_2") (pintype "passive"))
      (node (ref "C12") (pin "2") (pinfunction "2_2") (pintype "passive"))
      (node (ref "C13") (pin "2") (pinfunction "2_2") (pintype "passive"))
      (node (ref "C14") (pin "2") (pinfunction "2_2") (pintype "passive"))
      (node (ref "C15") (pin "2") (pinfunction "2_2") (pintype "passive"))
      (node (ref "C17") (pin "2") (pinfunction "2_2") (pintype "passive"))
      (node (ref "C18") (pin "2") (pinfunction "2_2") (pintype "passive"))
      (node (ref "C19") (pin "2") (pinfunction "2_2") (pintype "passive"))
      (node (ref "C20") (pin "2") (pinfunction "2_2") (pintype "passive"))
      (node (ref "C22") (pin "2") (pinfunction "2_2") (pintype "passive"))
      (node (ref "C23") (pin "2") (pinfunction "2_2") (pintype "passive"))
      (node (ref "C24") (pin "2") (pinfunction "2_2") (pintype "passive"))
      (node (ref "C25") (pin "2") (pinfunction "2_2") (pintype "passive"))
      (node (ref "D6") (pin "1") (pinfunction "A_1") (pintype "passive"))
      (node (ref "D6") (pin "3") (pinfunction "A_3") (pintype "passive"))
      (node (ref "D7") (pin "2") (pinfunction "A_2") (pintype "passive"))
      (node (ref "J1") (pin "1") (pinfunction "1_1") (pintype "passive"))
      (node (ref "J1") (pin "2") (pinfunction "2_2") (pintype "passive"))
      (node (ref "J1") (pin "3") (pinfunction "3_3") (pintype "passive"))
      (node (ref "J1") (pin "4") (pinfunction "4_4") (pintype "passive"))
      (node (ref "J1") (pin "5") (pinfunction "5_5") (pintype "passive"))
      (node (ref "J2") (pin "1") (pinfunction "1_1") (pintype "passive"))
      (node (ref "R14") (pin "1") (pinfunction "1_1") (pintype "passive"))
    )
    (net (code "30") (name "PACK_PLUS") (class "Default")
      (node (ref "C10") (pin "2") (pinfunction "2_2") (pintype "passive"))
      (node (ref "C11") (pin "1") (pinfunction "1_1") (pintype "passive"))
      (node (ref "C12") (pin "1") (pinfunction "1_1") (pintype "passive"))
      (node (ref "C14") (pin "1") (pinfunction "1_1") (pintype "passive"))
      (node (ref "C15") (pin "1") (pinfunction "1_1") (pintype "passive"))
      (node (ref "C16") (pin "1") (pinfunction "1_1") (pintype "passive"))
      (node (ref "C17") (pin "1") (pinfunction "1_1") (pintype "passive"))
      (node (ref "C18") (pin "1") (pinfunction "1_1") (pintype "passive"))
      (node (ref "C19") (pin "1") (pinfunction "1_1") (pintype "passive"))
      (node (ref "C20") (pin "1") (pinfunction "1_1") (pintype "passive"))
      (node (ref "C21") (pin "1") (pinfunction "1_1") (pintype "passive"))
      (node (ref "C22") (pin "1") (pinfunction "1_1") (pintype "passive"))
      (node (ref "C23") (pin "1") (pinfunction "1_1") (pintype "passive"))
      (node (ref "C24") (pin "1") (pinfunction "1_1") (pintype "passive"))
      (node (ref "C25") (pin "1") (pinfunction "1_1") (pintype "passive"))
      (node (ref "D4") (pin "2") (pinfunction "2_2") (pintype "passive"))
      (node (ref "D6") (pin "2") (pinfunction "K_2") (pintype "passive"))
      (node (ref "D7") (pin "1") (pinfunction "K_1") (pintype "passive"))
      (node (ref "D8") (pin "2") (pinfunction "2_2") (pintype "passive"))
      (node (ref "J2") (pin "2") (pinfunction "2_2") (pintype "passive"))
      (node (ref "P1") (pin "1") (pinfunction "1_1") (pintype "passive"))
      (node (ref "Q3") (pin "1") (pinfunction "S_1") (pintype "passive"))
      (node (ref "Q3") (pin "2") (pinfunction "S_2") (pintype "passive"))
      (node (ref "Q3") (pin "3") (pinfunction "S_3") (pintype "passive"))
      (node (ref "Q4") (pin "3") (pinfunction "S_3") (pintype "passive"))
      (node (ref "Q5") (pin "3") (pinfunction "S_3") (pintype "passive"))
      (node (ref "R12") (pin "1") (pinfunction "1_1") (pintype "passive"))
      (node (ref "R13") (pin "1") (pinfunction "1_1") (pintype "passive"))
      (node (ref "R14") (pin "2") (pinfunction "2_2") (pintype "passive"))
      (node (ref "R17") (pin "1") (pinfunction "1_1") (pintype "passive"))
    )
    (net (code "31") (name "VC1") (class "Default")
      (node (ref "C1") (pin "1") (pinfunction "1_1") (pintype "passive"))
      (node (ref "R1") (pin "2") (pinfunction "2_2") (pintype "passive"))
    )
    (net (code "32") (name "VC2") (class "Default")
      (node (ref "C1") (pin "2") (pinfunction "2_2") (pintype "passive"))
      (node (ref "C2") (pin "1") (pinfunction "1_1") (pintype "passive"))
      (node (ref "R2") (pin "2") (pinfunction "2_2") (pintype "passive"))
    )
    (net (code "33") (name "VC3") (class "Default")
      (node (ref "C2") (pin "2") (pinfunction "2_2") (pintype "passive"))
      (node (ref "C3") (pin "1") (pinfunction "1_1") (pintype "passive"))
      (node (ref "R3") (pin "2") (pinfunction "2_2") (pintype "passive"))
    )
    (net (code "34") (name "VC4") (class "Default")
      (node (ref "C3") (pin "2") (pinfunction "2_2") (pintype "passive"))
      (node (ref "C4") (pin "1") (pinfunction "1_1") (pintype "passive"))
      (node (ref "R4") (pin "2") (pinfunction "2_2") (pintype "passive"))
    )
    (net (code "35") (name "VC5") (class "Default")
      (node (ref "C4") (pin "2") (pinfunction "2_2") (pintype "passive"))
      (node (ref "C5") (pin "1") (pinfunction "1_1") (pintype "passive"))
      (node (ref "R5") (pin "2") (pinfunction "2_2") (pintype "passive"))
    )
    (net (code "36") (name "VC6") (class "Default")
      (node (ref "C5") (pin "2") (pinfunction "2_2") (pintype "passive"))
      (node (ref "C6") (pin "1") (pinfunction "1_1") (pintype "passive"))
      (node (ref "R6") (pin "2") (pinfunction "2_2") (pintype "passive"))
    )
    (net (code "37") (name "VC7") (class "Default")
      (node (ref "C6") (pin "2") (pinfunction "2_2") (pintype "passive"))
      (node (ref "R7") (pin "2") (pinfunction "2_2") (pintype "passive"))
    )
  )
)
